# USBC.net
KiCad netlist of a schematic drawn in Altium Designer
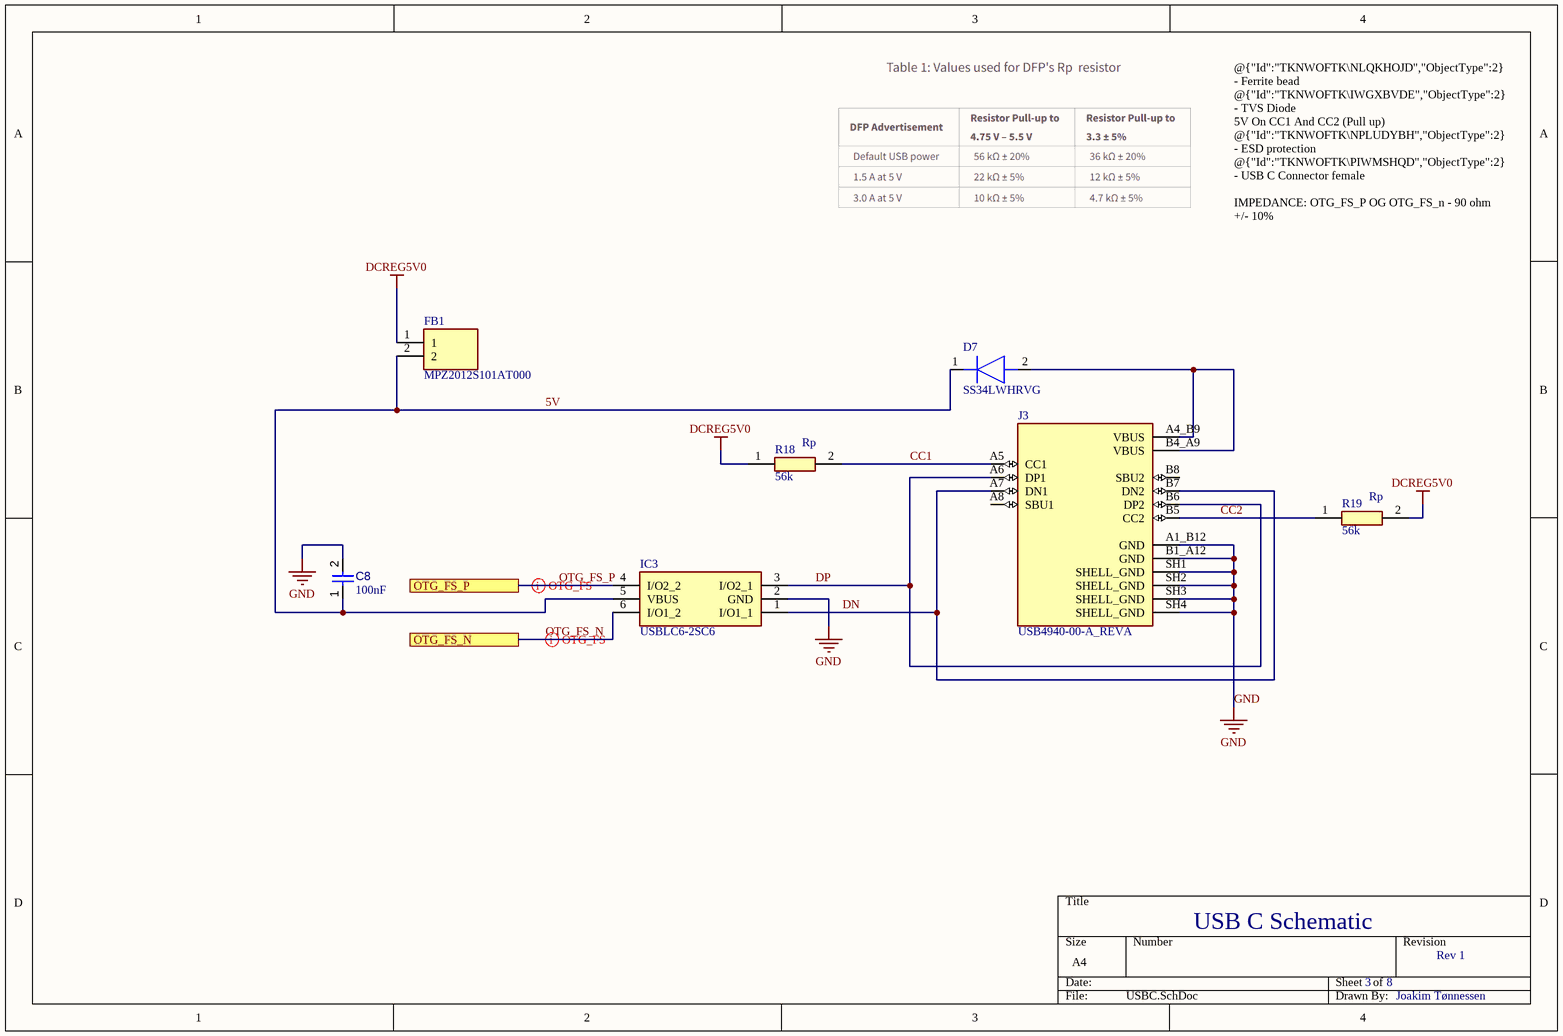
[diagram p0: USBC.SchDoc]

(export (version "E")
  (design (tool "Eeschema 10.0.6"))
  (components
    (comp (ref "C8")
      (value "100nF")
      (footprint "CAPC2012X09N")
      (description "Cap Ceramic 0.1uF 25V X7R 5% SMD 0805 FlexiTerm 125°C Paper T/R")
      (fields (field (name "TOLERANCE") "5%") (field (name "Comment") "08053C104JAZ2A"))
      (libsource (lib "UiS Aerospace") (part "CAP-NP-2"))
    )
    (comp (ref "D7")
      (value "SS34LWHRVG")
      (footprint "SamacSys:SODFL3718X102N")
      (description "Diode")
      (fields (field (name "MOUSER PART NUMBER") "821-SS34LWHRVG"))
      (libsource (lib "*") (part "SS34LWHRVG"))
    )
    (comp (ref "FB1")
      (value "MPZ2012S101AT000")
      (footprint "SamacSys:BEADC2012X105N")
      (description "Ferrite Bead")
      (fields (field (name "MOUSER PART NUMBER") "810-MPZ2012S101AT000"))
      (libsource (lib "*") (part "MPZ2012S101AT000"))
    )
    (comp (ref "IC3")
      (value "USBLC6-2SC6")
      (footprint "SamacSys:SOT95P280X145-6N")
      (description "Integrated Circuit")
      (fields (field (name "MOUSER PART NUMBER") "511-USBLC6-2SC6"))
      (libsource (lib "*") (part "USBLC6-2SC6"))
    )
    (comp (ref "J3")
      (value "USB4940-00-A_REVA")
      (footprint "GCT_USB4940-00-A_REVA")
      (description "Type C USB 2.0 Connector")
      (fields (field (name "MP") "USB4940-00-A") (field (name "MF") "Global Connector Technology"))
      (libsource (lib "UiS Aerospace") (part "USB4940-00-A_REVA"))
    )
    (comp (ref "R18")
      (value "56k")
      (footprint "SamacSys:RESC1608X50N")
      (description "Resistor\r\nCRCW060356K0JNEA")
      (fields
        (field (name "MANUFACTURER_PART_NUMBER") "CRCW060356K0JNEA")
        (field (name "MOUSER PART NUMBER") "71-CRCW060356K0JNEA")
      )
      (libsource (lib "*") (part "CRCW060356K0JNEA"))
    )
    (comp (ref "R19")
      (value "56k")
      (footprint "SamacSys:RESC1608X50N")
      (description "Resistor\r\nCRCW060356K0JNEA")
      (fields
        (field (name "MANUFACTURER_PART_NUMBER") "CRCW060356K0JNEA")
        (field (name "MOUSER PART NUMBER") "71-CRCW060356K0JNEA")
      )
      (libsource (lib "*") (part "CRCW060356K0JNEA"))
    )
  )
  (nets
    (net (code "1") (name "/5V") (class "Default")
      (node (ref "C8") (pin "1") (pinfunction "1_1") (pintype "passive"))
      (node (ref "D7") (pin "1") (pinfunction "K_1") (pintype "passive"))
      (node (ref "FB1") (pin "2") (pinfunction "2_2") (pintype "passive"))
      (node (ref "IC3") (pin "5") (pinfunction "VBUS_5") (pintype "passive"))
    )
    (net (code "2") (name "/CC1") (class "Default")
      (node (ref "J3") (pin "A5") (pinfunction "CC1_A5") (pintype "bidirectional"))
      (node (ref "R18") (pin "2") (pinfunction "2_2") (pintype "passive"))
    )
    (net (code "3") (name "/CC2") (class "Default")
      (node (ref "J3") (pin "B5") (pinfunction "CC2_B5") (pintype "bidirectional"))
      (node (ref "R19") (pin "1") (pinfunction "1_1") (pintype "passive"))
    )
    (net (code "4") (name "/DN") (class "Default")
      (node (ref "IC3") (pin "1") (pinfunction "I/O1_1_1") (pintype "passive"))
      (node (ref "J3") (pin "A7") (pinfunction "DN1_A7") (pintype "bidirectional"))
      (node (ref "J3") (pin "B7") (pinfunction "DN2_B7") (pintype "bidirectional"))
    )
    (net (code "5") (name "/DP") (class "Default")
      (node (ref "IC3") (pin "3") (pinfunction "I/O2_1_3") (pintype "passive"))
      (node (ref "J3") (pin "A6") (pinfunction "DP1_A6") (pintype "bidirectional"))
      (node (ref "J3") (pin "B6") (pinfunction "DP2_B6") (pintype "bidirectional"))
    )
    (net (code "6") (name "/OTG_FS_N") (class "Default")
      (node (ref "IC3") (pin "6") (pinfunction "I/O1_2_6") (pintype "passive"))
    )
    (net (code "7") (name "/OTG_FS_P") (class "Default")
      (node (ref "IC3") (pin "4") (pinfunction "I/O2_2_4") (pintype "passive"))
    )
    (net (code "8") (name "DCREG5V0") (class "Default")
      (node (ref "FB1") (pin "1") (pinfunction "1_1") (pintype "passive"))
      (node (ref "R18") (pin "1") (pinfunction "1_1") (pintype "passive"))
      (node (ref "R19") (pin "2") (pinfunction "2_2") (pintype "passive"))
    )
    (net (code "9") (name "GND") (class "Default")
      (node (ref "C8") (pin "2") (pinfunction "2_2") (pintype "passive"))
      (node (ref "IC3") (pin "2") (pinfunction "GND_2") (pintype "passive"))
      (node (ref "J3") (pin "A1_B12") (pinfunction "GND_A1_B12") (pintype "power_in"))
      (node (ref "J3") (pin "B1_A12") (pinfunction "GND_B1_A12") (pintype "power_in"))
      (node (ref "J3") (pin "SH1") (pinfunction "SHELL_GND_SH1") (pintype "power_in"))
      (node (ref "J3") (pin "SH2") (pinfunction "SHELL_GND_SH2") (pintype "power_in"))
      (node (ref "J3") (pin "SH3") (pinfunction "SHELL_GND_SH3") (pintype "power_in"))
      (node (ref "J3") (pin "SH4") (pinfunction "SHELL_GND_SH4") (pintype "power_in"))
    )
    (net (code "10") (name "Net-(D7-A)") (class "Default")
      (node (ref "D7") (pin "2") (pinfunction "A_2") (pintype "passive"))
      (node (ref "J3") (pin "A4_B9") (pinfunction "VBUS_A4_B9") (pintype "power_in"))
      (node (ref "J3") (pin "B4_A9") (pinfunction "VBUS_B4_A9") (pintype "power_in"))
    )
    (net (code "11") (name "unconnected-(J3-SBU1-PadA8)") (class "Default")
      (node (ref "J3") (pin "A8") (pinfunction "SBU1_A8") (pintype "bidirectional"))
    )
    (net (code "12") (name "unconnected-(J3-SBU2-PadB8)") (class "Default")
      (node (ref "J3") (pin "B8") (pinfunction "SBU2_B8") (pintype "bidirectional"))
    )
  )
)
